# BNO055.net
KiCad netlist of a schematic drawn in EAGLE
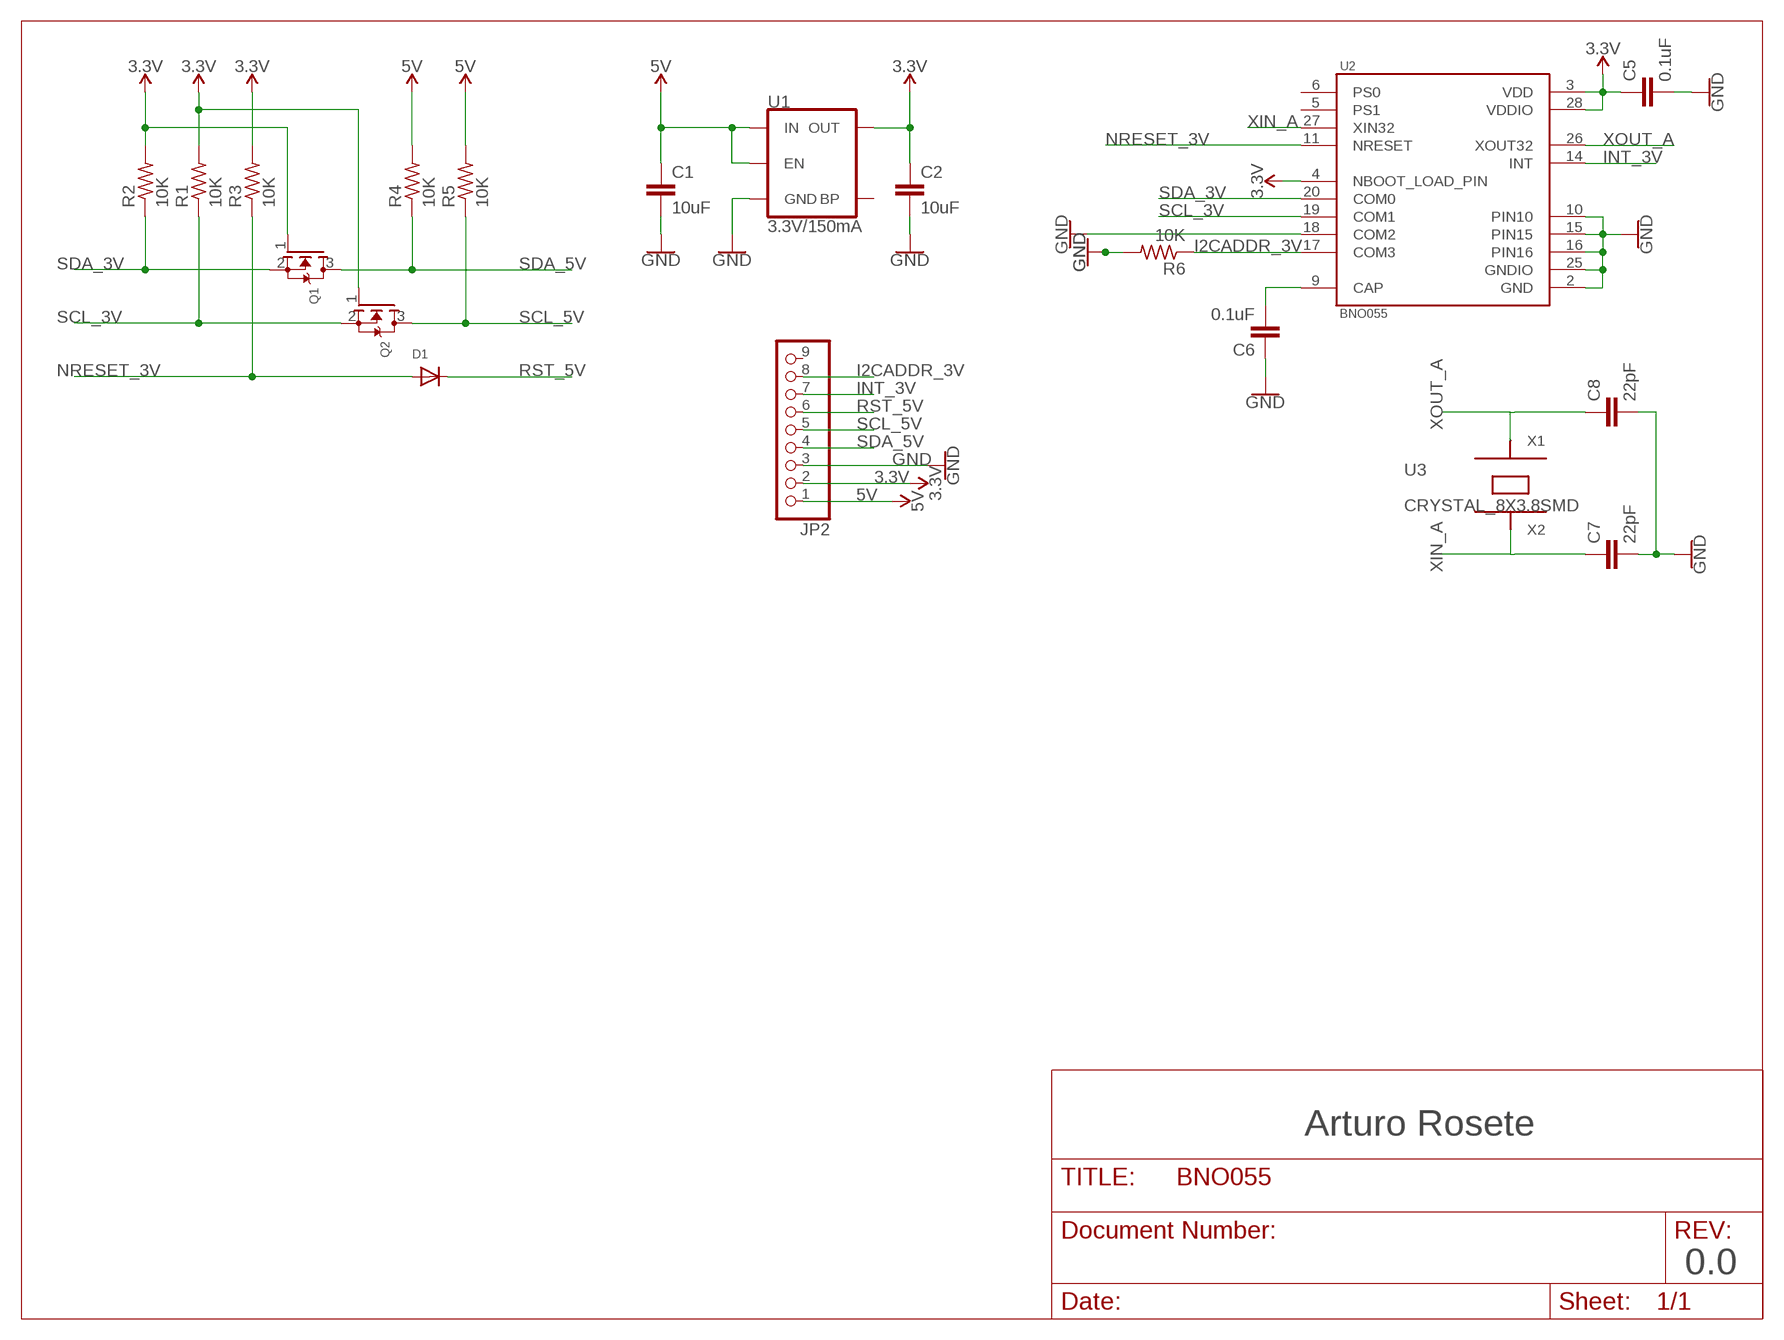
[diagram p0: schematic, sheet 1]

(export (version "E")
  (design (tool "Eeschema 10.0.6"))
  (components
    (comp (ref "C1")
      (value "10uF")
      (footprint "eagle-import:0805")
      (libsource (lib "eagle-import") (part "10UF-0805-10V-10%"))
    )
    (comp (ref "C2")
      (value "10uF")
      (footprint "eagle-import:0805")
      (libsource (lib "eagle-import") (part "10UF-0805-10V-10%"))
    )
    (comp (ref "C5")
      (value "0.1uF")
      (footprint "eagle-import:C0805")
      (libsource (lib "eagle-import") (part "C-EUC0805"))
    )
    (comp (ref "C6")
      (value "0.1uF")
      (footprint "eagle-import:C0805")
      (libsource (lib "eagle-import") (part "C-EUC0805"))
    )
    (comp (ref "C7")
      (value "22pF")
      (footprint "eagle-import:C0805")
      (libsource (lib "eagle-import") (part "C-EUC0805"))
    )
    (comp (ref "C8")
      (value "22pF")
      (footprint "eagle-import:C0805")
      (libsource (lib "eagle-import") (part "C-EUC0805"))
    )
    (comp (ref "D1")
      (value "DIODESOD-323F")
      (footprint "eagle-import:SOD-323F")
      (libsource (lib "eagle-import") (part "DIODESOD-323F"))
    )
    (comp (ref "JP2")
      (value "PINHD-1X9")
      (footprint "eagle-import:1X09-BIG")
      (libsource (lib "eagle-import") (part "PINHD-1X9"))
    )
    (comp (ref "Q1")
      (value "MOSFET-NWAVE")
      (footprint "eagle-import:SOT23-W")
      (libsource (lib "eagle-import") (part "MOSFET-NWAVE"))
    )
    (comp (ref "Q2")
      (value "MOSFET-NWAVE")
      (footprint "eagle-import:SOT23-W")
      (libsource (lib "eagle-import") (part "MOSFET-NWAVE"))
    )
    (comp (ref "R1")
      (value "10K")
      (footprint "eagle-import:R0805")
      (libsource (lib "eagle-import") (part "R-US_R0805"))
    )
    (comp (ref "R2")
      (value "10K")
      (footprint "eagle-import:R0805")
      (libsource (lib "eagle-import") (part "R-US_R0805"))
    )
    (comp (ref "R3")
      (value "10K")
      (footprint "eagle-import:R0805")
      (libsource (lib "eagle-import") (part "R-US_R0805"))
    )
    (comp (ref "R4")
      (value "10K")
      (footprint "eagle-import:R0805")
      (libsource (lib "eagle-import") (part "R-US_R0805"))
    )
    (comp (ref "R5")
      (value "10K")
      (footprint "eagle-import:R0805")
      (libsource (lib "eagle-import") (part "R-US_R0805"))
    )
    (comp (ref "R6")
      (value "10K")
      (footprint "eagle-import:R0805")
      (libsource (lib "eagle-import") (part "R-US_R0805"))
    )
    (comp (ref "U1")
      (value "3.3V/150mA")
      (footprint "eagle-import:SOT23-5")
      (libsource (lib "eagle-import") (part "V_REG_MIC52053.3V"))
    )
    (comp (ref "U2")
      (value "BNO055")
      (footprint "eagle-import:LGA28R50P4X10_380X520X100")
      (fields (field (name "DIGI-KEY_PART_NUMBER") "828-1058-1-ND") (field (name "MF") "Bosch"))
      (libsource (lib "eagle-import") (part "BNO055"))
    )
    (comp (ref "U3")
      (value "CRYSTAL_8X3.8SMD")
      (footprint "eagle-import:PM8.0X3.8MM")
      (libsource (lib "eagle-import") (part "CRYSTAL_8X3.8SMD"))
    )
  )
  (nets
    (net (code "1") (name "/I2CADDR_3V") (class "Default")
      (node (ref "JP2") (pin "8") (pinfunction "8_8") (pintype "passive"))
      (node (ref "R6") (pin "1") (pinfunction "1_1") (pintype "passive"))
      (node (ref "U2") (pin "17") (pinfunction "COM3_17") (pintype "bidirectional"))
    )
    (net (code "2") (name "/INT_3V") (class "Default")
      (node (ref "JP2") (pin "7") (pinfunction "7_7") (pintype "passive"))
      (node (ref "U2") (pin "14") (pinfunction "INT_14") (pintype "output"))
    )
    (net (code "3") (name "/NRESET_3V") (class "Default")
      (node (ref "D1") (pin "A") (pinfunction "A_A") (pintype "passive"))
      (node (ref "R3") (pin "1") (pinfunction "1_1") (pintype "passive"))
      (node (ref "U2") (pin "11") (pinfunction "NRESET_11") (pintype "input"))
    )
    (net (code "4") (name "/RST_5V") (class "Default")
      (node (ref "D1") (pin "C") (pinfunction "C_C") (pintype "passive"))
      (node (ref "JP2") (pin "6") (pinfunction "6_6") (pintype "passive"))
    )
    (net (code "5") (name "/SCL_3V") (class "Default")
      (node (ref "Q2") (pin "2") (pinfunction "S_2") (pintype "bidirectional"))
      (node (ref "R1") (pin "1") (pinfunction "1_1") (pintype "passive"))
      (node (ref "U2") (pin "19") (pinfunction "COM1_19") (pintype "bidirectional"))
    )
    (net (code "6") (name "/SCL_5V") (class "Default")
      (node (ref "JP2") (pin "5") (pinfunction "5_5") (pintype "passive"))
      (node (ref "Q2") (pin "3") (pinfunction "D_3") (pintype "bidirectional"))
      (node (ref "R5") (pin "1") (pinfunction "1_1") (pintype "passive"))
    )
    (net (code "7") (name "/SDA_3V") (class "Default")
      (node (ref "Q1") (pin "2") (pinfunction "S_2") (pintype "bidirectional"))
      (node (ref "R2") (pin "1") (pinfunction "1_1") (pintype "passive"))
      (node (ref "U2") (pin "20") (pinfunction "COM0_20") (pintype "bidirectional"))
    )
    (net (code "8") (name "/SDA_5V") (class "Default")
      (node (ref "JP2") (pin "4") (pinfunction "4_4") (pintype "passive"))
      (node (ref "Q1") (pin "3") (pinfunction "D_3") (pintype "bidirectional"))
      (node (ref "R4") (pin "1") (pinfunction "1_1") (pintype "passive"))
    )
    (net (code "9") (name "/XIN_A") (class "Default")
      (node (ref "C7") (pin "1") (pinfunction "1_1") (pintype "passive"))
      (node (ref "U2") (pin "27") (pinfunction "XIN32_27") (pintype "input"))
      (node (ref "U3") (pin "4") (pinfunction "X2_4") (pintype "bidirectional"))
    )
    (net (code "10") (name "/XOUT_A") (class "Default")
      (node (ref "C8") (pin "1") (pinfunction "1_1") (pintype "passive"))
      (node (ref "U2") (pin "26") (pinfunction "XOUT32_26") (pintype "output"))
      (node (ref "U3") (pin "1") (pinfunction "X1_1") (pintype "bidirectional"))
    )
    (net (code "11") (name "3.3V") (class "Default")
      (node (ref "C2") (pin "1") (pinfunction "1_1") (pintype "passive"))
      (node (ref "C5") (pin "1") (pinfunction "1_1") (pintype "passive"))
      (node (ref "JP2") (pin "2") (pinfunction "2_2") (pintype "passive"))
      (node (ref "Q1") (pin "1") (pinfunction "G_1") (pintype "bidirectional"))
      (node (ref "Q2") (pin "1") (pinfunction "G_1") (pintype "bidirectional"))
      (node (ref "R1") (pin "2") (pinfunction "2_2") (pintype "passive"))
      (node (ref "R2") (pin "2") (pinfunction "2_2") (pintype "passive"))
      (node (ref "R3") (pin "2") (pinfunction "2_2") (pintype "passive"))
      (node (ref "U1") (pin "5") (pinfunction "OUT_5") (pintype "passive"))
      (node (ref "U2") (pin "28") (pinfunction "VDDIO_28") (pintype "power_in"))
      (node (ref "U2") (pin "3") (pinfunction "VDD_3") (pintype "power_in"))
      (node (ref "U2") (pin "4") (pinfunction "NBOOT_LOAD_PIN_4") (pintype "bidirectional"))
    )
    (net (code "12") (name "5V") (class "Default")
      (node (ref "C1") (pin "1") (pinfunction "1_1") (pintype "passive"))
      (node (ref "JP2") (pin "1") (pinfunction "1_1") (pintype "passive"))
      (node (ref "R4") (pin "2") (pinfunction "2_2") (pintype "passive"))
      (node (ref "R5") (pin "2") (pinfunction "2_2") (pintype "passive"))
      (node (ref "U1") (pin "1") (pinfunction "IN_1") (pintype "input"))
      (node (ref "U1") (pin "3") (pinfunction "EN_3") (pintype "input"))
    )
    (net (code "13") (name "GND") (class "Default")
      (node (ref "C1") (pin "2") (pinfunction "2_2") (pintype "passive"))
      (node (ref "C2") (pin "2") (pinfunction "2_2") (pintype "passive"))
      (node (ref "C5") (pin "2") (pinfunction "2_2") (pintype "passive"))
      (node (ref "C6") (pin "1") (pinfunction "1_1") (pintype "passive"))
      (node (ref "C7") (pin "2") (pinfunction "2_2") (pintype "passive"))
      (node (ref "C8") (pin "2") (pinfunction "2_2") (pintype "passive"))
      (node (ref "JP2") (pin "3") (pinfunction "3_3") (pintype "passive"))
      (node (ref "R6") (pin "2") (pinfunction "2_2") (pintype "passive"))
      (node (ref "U1") (pin "2") (pinfunction "GND_2") (pintype "input"))
      (node (ref "U2") (pin "10") (pinfunction "PIN10_10") (pintype "power_in"))
      (node (ref "U2") (pin "15") (pinfunction "PIN15_15") (pintype "power_in"))
      (node (ref "U2") (pin "16") (pinfunction "PIN16_16") (pintype "power_in"))
      (node (ref "U2") (pin "18") (pinfunction "COM2_18") (pintype "bidirectional"))
      (node (ref "U2") (pin "2") (pinfunction "GND_2") (pintype "power_in"))
      (node (ref "U2") (pin "25") (pinfunction "GNDIO_25") (pintype "power_in"))
    )
    (net (code "14") (name "Net-(U2-CAP)") (class "Default")
      (node (ref "C6") (pin "2") (pinfunction "2_2") (pintype "passive"))
      (node (ref "U2") (pin "9") (pinfunction "CAP_9") (pintype "passive"))
    )
    (net (code "15") (name "unconnected-(JP2-Pad9)") (class "Default")
      (node (ref "JP2") (pin "9") (pinfunction "9_9") (pintype "passive"))
    )
    (net (code "16") (name "unconnected-(U1-BP-Pad4)") (class "Default")
      (node (ref "U1") (pin "4") (pinfunction "BP_4") (pintype "input"))
    )
    (net (code "17") (name "unconnected-(U2-PS0-Pad6)") (class "Default")
      (node (ref "U2") (pin "6") (pinfunction "PS0_6") (pintype "input"))
    )
    (net (code "18") (name "unconnected-(U2-PS1-Pad5)") (class "Default")
      (node (ref "U2") (pin "5") (pinfunction "PS1_5") (pintype "input"))
    )
  )
)
